# Sheet1.net
KiCad netlist of a schematic drawn in Altium Designer
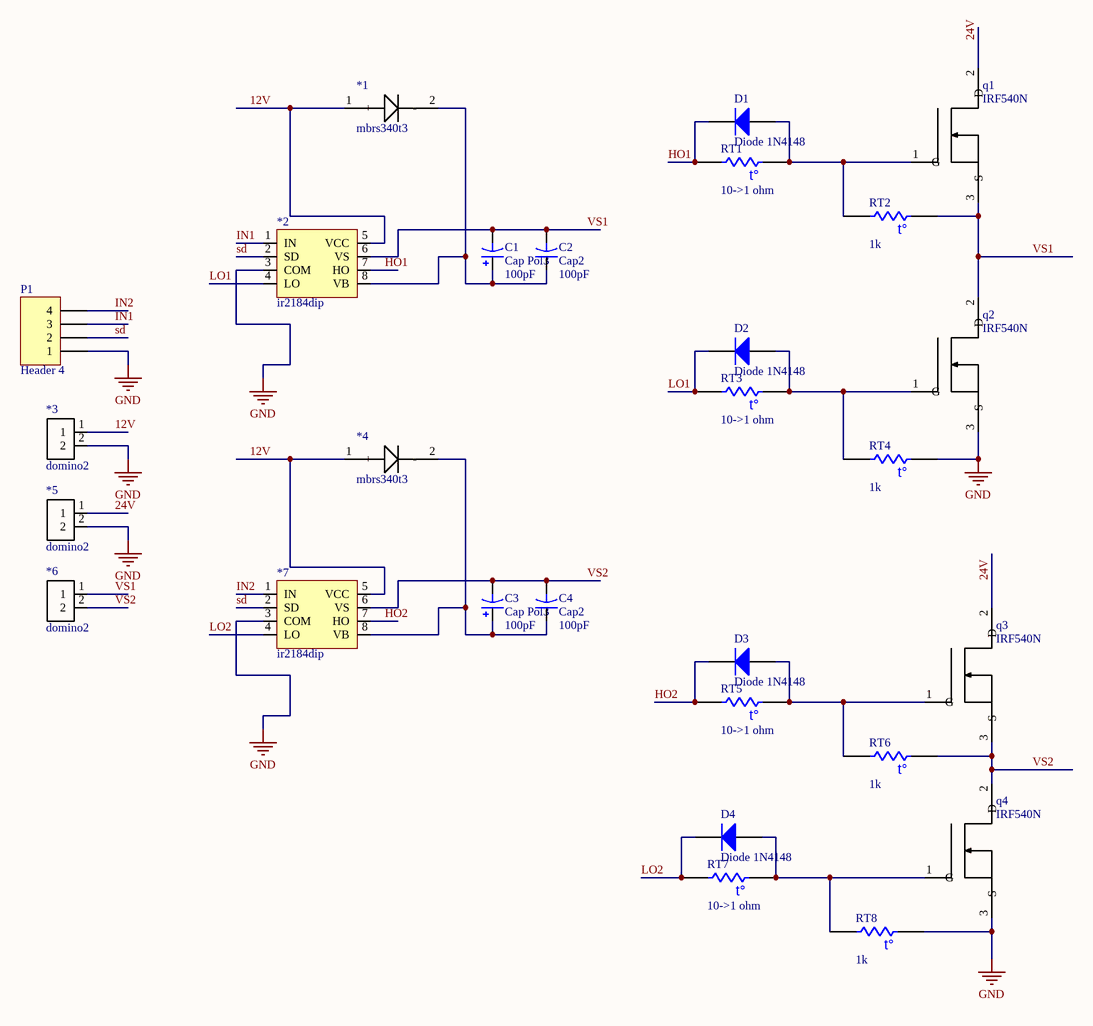
[diagram p0: Sheet1.SchDoc]

(export (version "E")
  (design (tool "Eeschema 10.0.6"))
  (components
    (comp (ref "*1")
      (value "mbrs340t3")
      (footprint "Pcbforslave:diode mbrs34ot3")
      (libsource (lib "Schlib1") (part "mbrs340t3"))
    )
    (comp (ref "*2") (value "ir2184dip") (footprint "ir2101") (libsource (lib "Schlib1") (part "ir2184dip")))
    (comp (ref "*3")
      (value "domino2")
      (footprint "Pcbforslave:Domino_2")
      (libsource (lib "Schlib1") (part "domino2"))
    )
    (comp (ref "*4")
      (value "mbrs340t3")
      (footprint "Pcbforslave:diode mbrs34ot3")
      (libsource (lib "Schlib1") (part "mbrs340t3"))
    )
    (comp (ref "*5")
      (value "domino2")
      (footprint "Pcbforslave:Domino_2")
      (libsource (lib "Schlib1") (part "domino2"))
    )
    (comp (ref "*6")
      (value "domino2")
      (footprint "Pcbforslave:Domino_2")
      (libsource (lib "Schlib1") (part "domino2"))
    )
    (comp (ref "*7") (value "ir2184dip") (footprint "ir2101") (libsource (lib "Schlib1") (part "ir2184dip")))
    (comp (ref "C1")
      (value "Cap Pol3")
      (footprint "C0805")
      (description "Polarized Capacitor (Surface Mount)")
      (fields (field (name "ALTIUM_VALUE") "100pF") (field (name "PUBLISHER") "Altium Limited"))
      (libsource (lib "Miscellaneous Devices") (part "Cap Pol3"))
    )
    (comp (ref "C2")
      (value "Cap2")
      (footprint "CAPR5-4X5")
      (description "Capacitor")
      (fields (field (name "ALTIUM_VALUE") "100pF") (field (name "PUBLISHER") "Altium Limited"))
      (libsource (lib "Miscellaneous Devices") (part "Cap2"))
    )
    (comp (ref "C3")
      (value "Cap Pol3")
      (footprint "C0805")
      (description "Polarized Capacitor (Surface Mount)")
      (fields (field (name "ALTIUM_VALUE") "100pF") (field (name "PUBLISHER") "Altium Limited"))
      (libsource (lib "Miscellaneous Devices") (part "Cap Pol3"))
    )
    (comp (ref "C4")
      (value "Cap2")
      (footprint "CAPR5-4X5")
      (description "Capacitor")
      (fields (field (name "ALTIUM_VALUE") "100pF") (field (name "PUBLISHER") "Altium Limited"))
      (libsource (lib "Miscellaneous Devices") (part "Cap2"))
    )
    (comp (ref "D1")
      (value "Diode 1N4148")
      (footprint "DO-35")
      (description "High Conductance Fast Diode")
      (fields (field (name "PUBLISHER") "Altium Limited"))
      (libsource (lib "Miscellaneous Devices") (part "Diode 1N4148"))
    )
    (comp (ref "D2")
      (value "Diode 1N4148")
      (footprint "DO-35")
      (description "High Conductance Fast Diode")
      (fields (field (name "PUBLISHER") "Altium Limited"))
      (libsource (lib "Miscellaneous Devices") (part "Diode 1N4148"))
    )
    (comp (ref "D3")
      (value "Diode 1N4148")
      (footprint "DO-35")
      (description "High Conductance Fast Diode")
      (fields (field (name "PUBLISHER") "Altium Limited"))
      (libsource (lib "Miscellaneous Devices") (part "Diode 1N4148"))
    )
    (comp (ref "D4")
      (value "Diode 1N4148")
      (footprint "DO-35")
      (description "High Conductance Fast Diode")
      (fields (field (name "PUBLISHER") "Altium Limited"))
      (libsource (lib "Miscellaneous Devices") (part "Diode 1N4148"))
    )
    (comp (ref "P1")
      (value "Header 4")
      (footprint "HDR1X4")
      (description "Header, 4-Pin")
      (fields (field (name "PUBLISHER") "Altium Limited"))
      (libsource (lib "Miscellaneous Connectors") (part "Header 4"))
    )
    (comp (ref "q1") (value "IRF540N") (footprint "TO220") (libsource (lib "Schlib1") (part "IRF540N")))
    (comp (ref "q2") (value "IRF540N") (footprint "TO220") (libsource (lib "Schlib1") (part "IRF540N")))
    (comp (ref "q3") (value "IRF540N") (footprint "TO220") (libsource (lib "Schlib1") (part "IRF540N")))
    (comp (ref "q4") (value "IRF540N") (footprint "TO220") (libsource (lib "Schlib1") (part "IRF540N")))
    (comp (ref "RT1")
      (value "10->1 ohm")
      (footprint "6-0805_N")
      (description "Thermistor")
      (fields (field (name "PUBLISHER") "Altium Limited"))
      (libsource (lib "Miscellaneous Devices") (part "Res Thermal"))
    )
    (comp (ref "RT2")
      (value "1k")
      (footprint "6-0805_N")
      (description "Thermistor")
      (fields (field (name "PUBLISHER") "Altium Limited"))
      (libsource (lib "Miscellaneous Devices") (part "Res Thermal"))
    )
    (comp (ref "RT3")
      (value "10->1 ohm")
      (footprint "6-0805_N")
      (description "Thermistor")
      (fields (field (name "PUBLISHER") "Altium Limited"))
      (libsource (lib "Miscellaneous Devices") (part "Res Thermal"))
    )
    (comp (ref "RT4")
      (value "1k")
      (footprint "6-0805_N")
      (description "Thermistor")
      (fields (field (name "PUBLISHER") "Altium Limited"))
      (libsource (lib "Miscellaneous Devices") (part "Res Thermal"))
    )
    (comp (ref "RT5")
      (value "10->1 ohm")
      (footprint "6-0805_N")
      (description "Thermistor")
      (fields (field (name "PUBLISHER") "Altium Limited"))
      (libsource (lib "Miscellaneous Devices") (part "Res Thermal"))
    )
    (comp (ref "RT6")
      (value "1k")
      (footprint "6-0805_N")
      (description "Thermistor")
      (fields (field (name "PUBLISHER") "Altium Limited"))
      (libsource (lib "Miscellaneous Devices") (part "Res Thermal"))
    )
    (comp (ref "RT7")
      (value "10->1 ohm")
      (footprint "6-0805_N")
      (description "Thermistor")
      (fields (field (name "PUBLISHER") "Altium Limited"))
      (libsource (lib "Miscellaneous Devices") (part "Res Thermal"))
    )
    (comp (ref "RT8")
      (value "1k")
      (footprint "6-0805_N")
      (description "Thermistor")
      (fields (field (name "PUBLISHER") "Altium Limited"))
      (libsource (lib "Miscellaneous Devices") (part "Res Thermal"))
    )
  )
  (nets
    (net (code "1") (name "/12V") (class "Default")
      (node (ref "*1") (pin "1") (pinfunction "+_1") (pintype "passive"))
      (node (ref "*2") (pin "5") (pinfunction "VCC_5") (pintype "passive"))
      (node (ref "*3") (pin "1") (pinfunction "1_1") (pintype "passive"))
      (node (ref "*4") (pin "1") (pinfunction "+_1") (pintype "passive"))
      (node (ref "*7") (pin "5") (pinfunction "VCC_5") (pintype "passive"))
    )
    (net (code "2") (name "/24V") (class "Default")
      (node (ref "*5") (pin "1") (pinfunction "1_1") (pintype "passive"))
      (node (ref "q1") (pin "2") (pinfunction "D_2") (pintype "passive"))
      (node (ref "q3") (pin "2") (pinfunction "D_2") (pintype "passive"))
    )
    (net (code "3") (name "/HO1") (class "Default")
      (node (ref "*2") (pin "7") (pinfunction "HO_7") (pintype "passive"))
      (node (ref "D1") (pin "2") (pinfunction "K_2") (pintype "passive"))
      (node (ref "RT1") (pin "2") (pinfunction "2_2") (pintype "passive"))
    )
    (net (code "4") (name "/HO2") (class "Default")
      (node (ref "*7") (pin "7") (pinfunction "HO_7") (pintype "passive"))
      (node (ref "D3") (pin "2") (pinfunction "K_2") (pintype "passive"))
      (node (ref "RT5") (pin "2") (pinfunction "2_2") (pintype "passive"))
    )
    (net (code "5") (name "/IN1") (class "Default")
      (node (ref "*2") (pin "1") (pinfunction "IN_1") (pintype "passive"))
      (node (ref "P1") (pin "3") (pinfunction "3_3") (pintype "passive"))
    )
    (net (code "6") (name "/IN2") (class "Default")
      (node (ref "*7") (pin "1") (pinfunction "IN_1") (pintype "passive"))
      (node (ref "P1") (pin "4") (pinfunction "4_4") (pintype "passive"))
    )
    (net (code "7") (name "/LO1") (class "Default")
      (node (ref "*2") (pin "4") (pinfunction "LO_4") (pintype "passive"))
      (node (ref "D2") (pin "2") (pinfunction "K_2") (pintype "passive"))
      (node (ref "RT3") (pin "2") (pinfunction "2_2") (pintype "passive"))
    )
    (net (code "8") (name "/LO2") (class "Default")
      (node (ref "*7") (pin "4") (pinfunction "LO_4") (pintype "passive"))
      (node (ref "D4") (pin "2") (pinfunction "K_2") (pintype "passive"))
      (node (ref "RT7") (pin "2") (pinfunction "2_2") (pintype "passive"))
    )
    (net (code "9") (name "/VS1") (class "Default")
      (node (ref "*2") (pin "6") (pinfunction "VS_6") (pintype "passive"))
      (node (ref "*6") (pin "1") (pinfunction "1_1") (pintype "passive"))
      (node (ref "C1") (pin "2") (pinfunction "2_2") (pintype "passive"))
      (node (ref "C2") (pin "2") (pinfunction "2_2") (pintype "passive"))
      (node (ref "RT2") (pin "1") (pinfunction "1_1") (pintype "passive"))
      (node (ref "q1") (pin "3") (pinfunction "S_3") (pintype "passive"))
      (node (ref "q2") (pin "2") (pinfunction "D_2") (pintype "passive"))
    )
    (net (code "10") (name "/VS2") (class "Default")
      (node (ref "*6") (pin "2") (pinfunction "2_2") (pintype "passive"))
      (node (ref "*7") (pin "6") (pinfunction "VS_6") (pintype "passive"))
      (node (ref "C3") (pin "2") (pinfunction "2_2") (pintype "passive"))
      (node (ref "C4") (pin "2") (pinfunction "2_2") (pintype "passive"))
      (node (ref "RT6") (pin "1") (pinfunction "1_1") (pintype "passive"))
      (node (ref "q3") (pin "3") (pinfunction "S_3") (pintype "passive"))
      (node (ref "q4") (pin "2") (pinfunction "D_2") (pintype "passive"))
    )
    (net (code "11") (name "/sd") (class "Default")
      (node (ref "*2") (pin "2") (pinfunction "SD_2") (pintype "passive"))
      (node (ref "*7") (pin "2") (pinfunction "SD_2") (pintype "passive"))
      (node (ref "P1") (pin "2") (pinfunction "2_2") (pintype "passive"))
    )
    (net (code "12") (name "GND") (class "Default")
      (node (ref "*2") (pin "3") (pinfunction "COM_3") (pintype "passive"))
      (node (ref "*3") (pin "2") (pinfunction "2_2") (pintype "passive"))
      (node (ref "*5") (pin "2") (pinfunction "2_2") (pintype "passive"))
      (node (ref "*7") (pin "3") (pinfunction "COM_3") (pintype "passive"))
      (node (ref "P1") (pin "1") (pinfunction "1_1") (pintype "passive"))
      (node (ref "RT4") (pin "1") (pinfunction "1_1") (pintype "passive"))
      (node (ref "RT8") (pin "1") (pinfunction "1_1") (pintype "passive"))
      (node (ref "q2") (pin "3") (pinfunction "S_3") (pintype "passive"))
      (node (ref "q4") (pin "3") (pinfunction "S_3") (pintype "passive"))
    )
    (net (code "13") (name "Net-(*1--)") (class "Default")
      (node (ref "*1") (pin "2") (pinfunction "-_2") (pintype "passive"))
      (node (ref "*2") (pin "8") (pinfunction "VB_8") (pintype "passive"))
      (node (ref "C1") (pin "1") (pinfunction "1_1") (pintype "passive"))
      (node (ref "C2") (pin "1") (pinfunction "1_1") (pintype "passive"))
    )
    (net (code "14") (name "Net-(*4--)") (class "Default")
      (node (ref "*4") (pin "2") (pinfunction "-_2") (pintype "passive"))
      (node (ref "*7") (pin "8") (pinfunction "VB_8") (pintype "passive"))
      (node (ref "C3") (pin "1") (pinfunction "1_1") (pintype "passive"))
      (node (ref "C4") (pin "1") (pinfunction "1_1") (pintype "passive"))
    )
    (net (code "15") (name "Net-(D1-A)") (class "Default")
      (node (ref "D1") (pin "1") (pinfunction "A_1") (pintype "passive"))
      (node (ref "RT1") (pin "1") (pinfunction "1_1") (pintype "passive"))
      (node (ref "RT2") (pin "2") (pinfunction "2_2") (pintype "passive"))
      (node (ref "q1") (pin "1") (pinfunction "G_1") (pintype "passive"))
    )
    (net (code "16") (name "Net-(D2-A)") (class "Default")
      (node (ref "D2") (pin "1") (pinfunction "A_1") (pintype "passive"))
      (node (ref "RT3") (pin "1") (pinfunction "1_1") (pintype "passive"))
      (node (ref "RT4") (pin "2") (pinfunction "2_2") (pintype "passive"))
      (node (ref "q2") (pin "1") (pinfunction "G_1") (pintype "passive"))
    )
    (net (code "17") (name "Net-(D3-A)") (class "Default")
      (node (ref "D3") (pin "1") (pinfunction "A_1") (pintype "passive"))
      (node (ref "RT5") (pin "1") (pinfunction "1_1") (pintype "passive"))
      (node (ref "RT6") (pin "2") (pinfunction "2_2") (pintype "passive"))
      (node (ref "q3") (pin "1") (pinfunction "G_1") (pintype "passive"))
    )
    (net (code "18") (name "Net-(D4-A)") (class "Default")
      (node (ref "D4") (pin "1") (pinfunction "A_1") (pintype "passive"))
      (node (ref "RT7") (pin "1") (pinfunction "1_1") (pintype "passive"))
      (node (ref "RT8") (pin "2") (pinfunction "2_2") (pintype "passive"))
      (node (ref "q4") (pin "1") (pinfunction "G_1") (pintype "passive"))
    )
  )
)
